# Pioneer_Kit_Shield.net
KiCad netlist of a schematic drawn in EAGLE
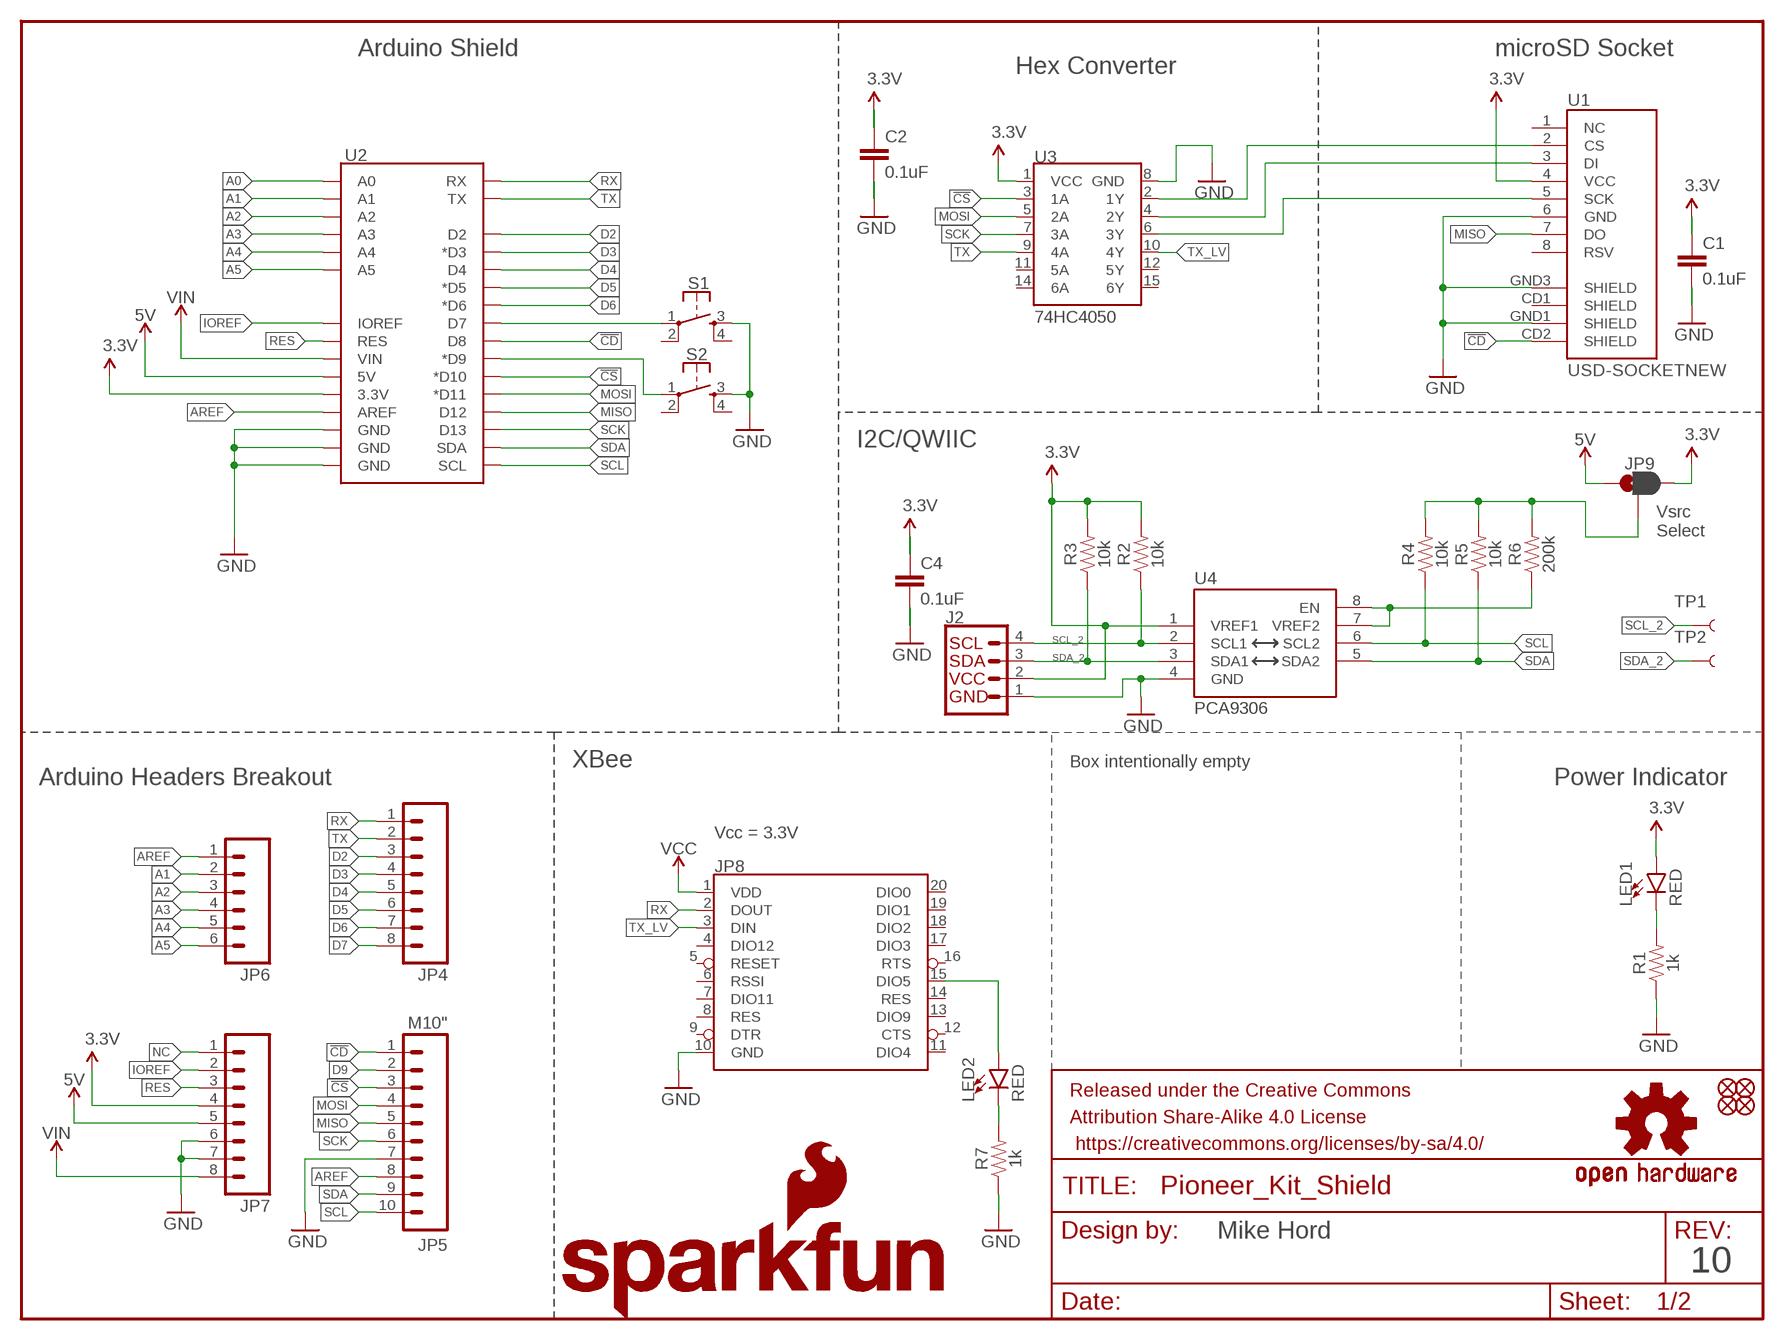
[diagram p0: schematic, sheet 1]
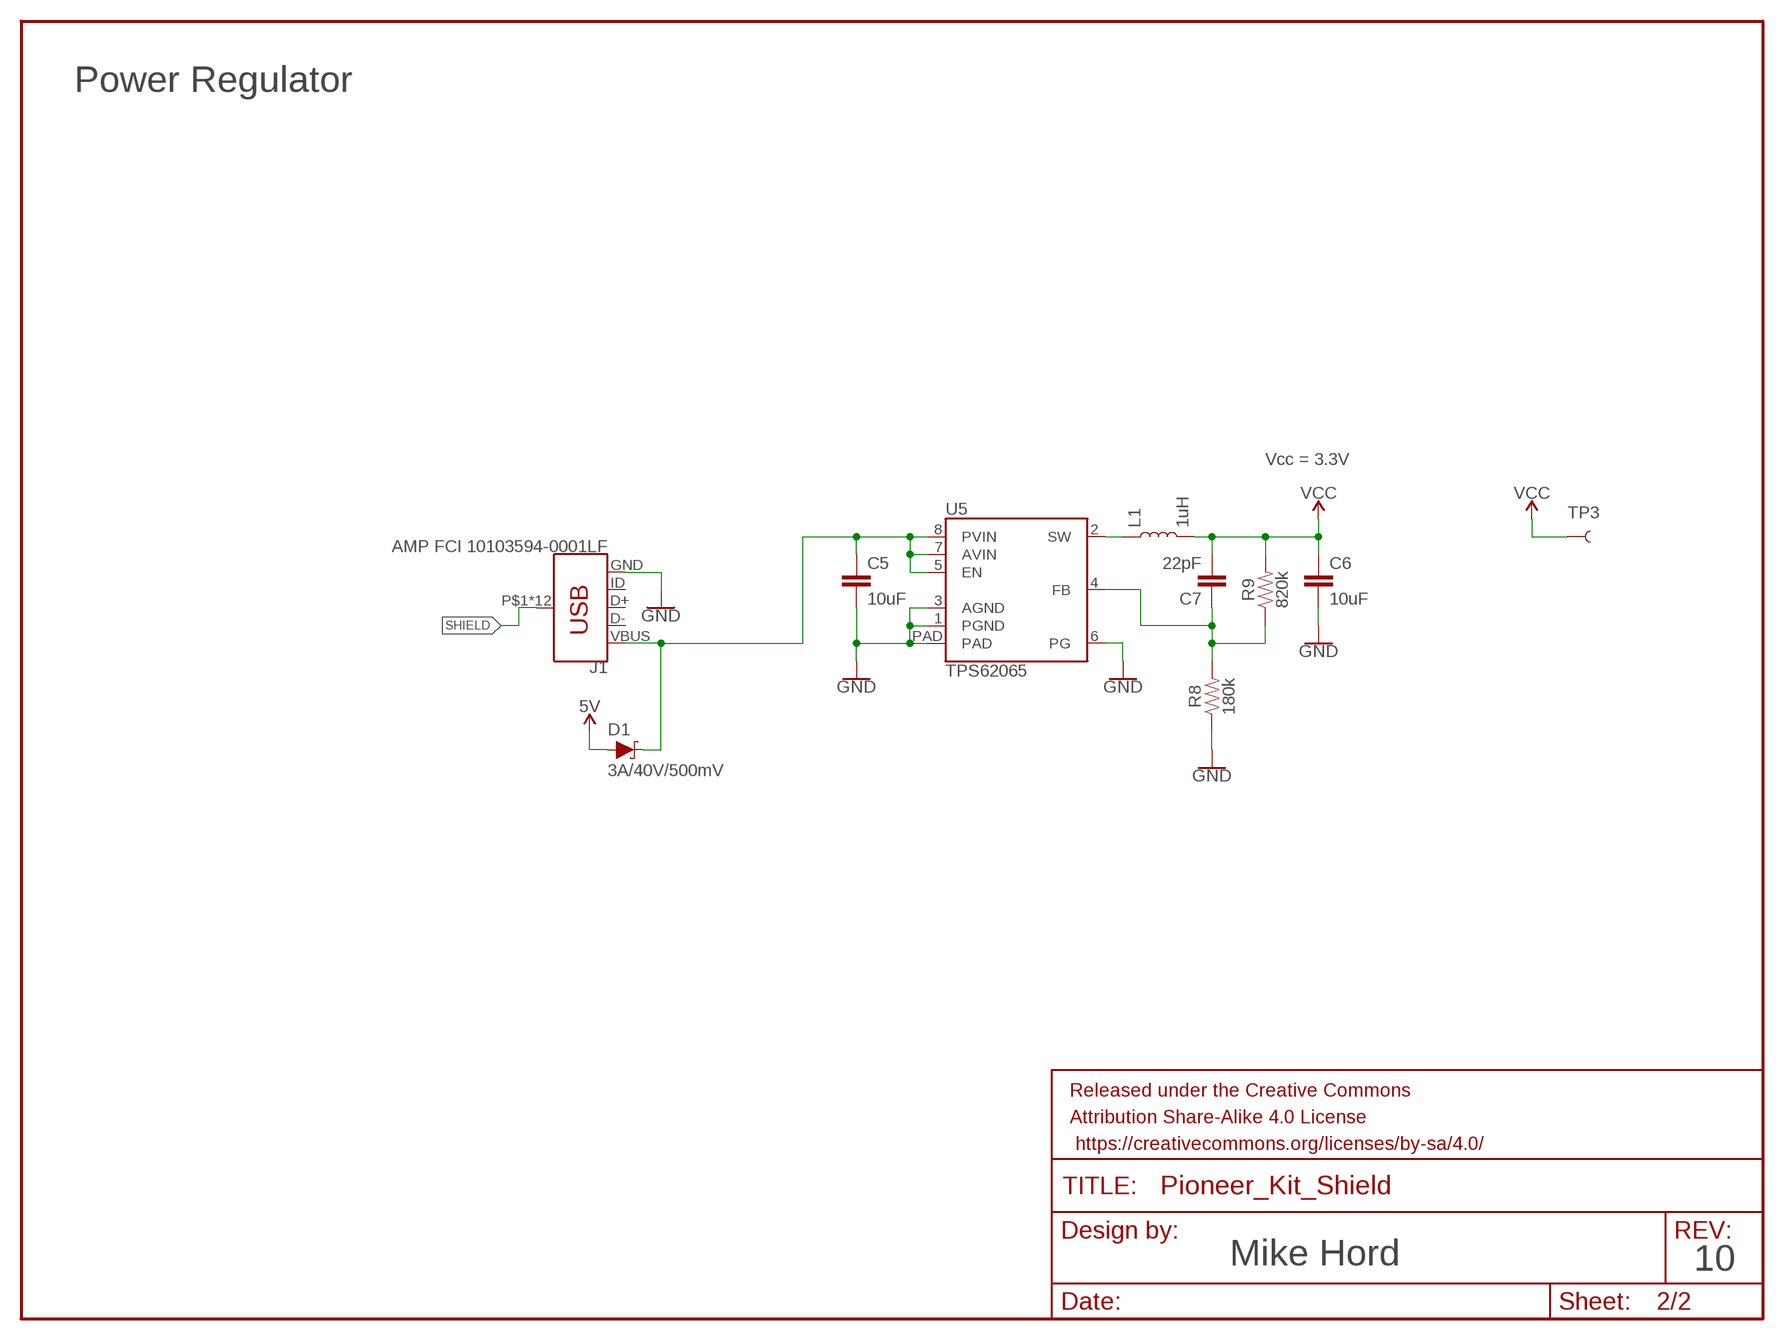
[diagram p1: schematic, sheet 2]

(export (version "E")
  (design (tool "Eeschema 10.0.6"))
  (components
    (comp (ref "C1")
      (value "0.1uF")
      (footprint "eagle-import:0603")
      (libsource (lib "eagle-import") (part "0.1UF-0603-25V-5%"))
    )
    (comp (ref "C2")
      (value "0.1uF")
      (footprint "eagle-import:0603")
      (libsource (lib "eagle-import") (part "0.1UF-0603-25V-5%"))
    )
    (comp (ref "C4")
      (value "0.1uF")
      (footprint "eagle-import:0603")
      (libsource (lib "eagle-import") (part "0.1UF-0603-25V-5%"))
    )
    (comp (ref "FRAME1")
      (value "FRAME-LETTER")
      (footprint "eagle-import:CREATIVE_COMMONS")
      (libsource (lib "eagle-import") (part "FRAME-LETTER"))
    )
    (comp (ref "J2")
      (value "QWIIC_CONNECTORJS-1MM")
      (footprint "eagle-import:1X04_1MM_RA")
      (libsource (lib "eagle-import") (part "QWIIC_CONNECTORJS-1MM"))
    )
    (comp (ref "JP1")
      (value "SFE_LOGO_NAME_FLAME.1_INCH")
      (footprint "eagle-import:SFE_LOGO_NAME_FLAME_.1")
      (libsource (lib "eagle-import") (part "SFE_LOGO_NAME_FLAME.1_INCH"))
    )
    (comp (ref "JP2")
      (value "FIDUCIAL1X2")
      (footprint "eagle-import:FIDUCIAL-1X2")
      (libsource (lib "eagle-import") (part "FIDUCIAL1X2"))
    )
    (comp (ref "JP3")
      (value "FIDUCIAL1X2")
      (footprint "eagle-import:FIDUCIAL-1X2")
      (libsource (lib "eagle-import") (part "FIDUCIAL1X2"))
    )
    (comp (ref "JP4")
      (value "M08")
      (footprint "eagle-import:1X08")
      (libsource (lib "eagle-import") (part "M08"))
    )
    (comp (ref "JP5")
      (value "M10\"")
      (footprint "eagle-import:1X10")
      (libsource (lib "eagle-import") (part "M10{dblquote}"))
    )
    (comp (ref "JP6")
      (value "M06SIP")
      (footprint "eagle-import:1X06")
      (libsource (lib "eagle-import") (part "M06SIP"))
    )
    (comp (ref "JP7")
      (value "M081X08")
      (footprint "eagle-import:1X08")
      (libsource (lib "eagle-import") (part "M081X08"))
    )
    (comp (ref "JP8")
      (value "XBEESMD")
      (footprint "eagle-import:XBEE-SMD")
      (libsource (lib "eagle-import") (part "XBEESMD"))
    )
    (comp (ref "JP9")
      (value "JUMPER-SMT_3_1-NC_PASTE_SILK")
      (footprint "eagle-import:SMT-JUMPER_3_1-NC_PASTE_SILK")
      (libsource (lib "eagle-import") (part "JUMPER-SMT_3_1-NC_PASTE_SILK"))
    )
    (comp (ref "JP10")
      (value "FIDUCIAL1X2")
      (footprint "eagle-import:FIDUCIAL-1X2")
      (libsource (lib "eagle-import") (part "FIDUCIAL1X2"))
    )
    (comp (ref "JP11")
      (value "FIDUCIAL1X2")
      (footprint "eagle-import:FIDUCIAL-1X2")
      (libsource (lib "eagle-import") (part "FIDUCIAL1X2"))
    )
    (comp (ref "LED1")
      (value "RED")
      (footprint "eagle-import:LED-0603")
      (libsource (lib "eagle-import") (part "LED-RED0603"))
    )
    (comp (ref "LED2")
      (value "RED")
      (footprint "eagle-import:LED-0603")
      (libsource (lib "eagle-import") (part "LED-RED0603"))
    )
    (comp (ref "LOGO1")
      (value "OSHW-LOGOM")
      (footprint "eagle-import:OSHW-LOGO-M")
      (libsource (lib "eagle-import") (part "OSHW-LOGOM"))
    )
    (comp (ref "R1")
      (value "1k")
      (footprint "eagle-import:0603")
      (libsource (lib "eagle-import") (part "1KOHM-0603-1/10W-1%"))
    )
    (comp (ref "R2")
      (value "10k")
      (footprint "eagle-import:0603")
      (libsource (lib "eagle-import") (part "10KOHM-0603-1/10W-1%"))
    )
    (comp (ref "R3")
      (value "10k")
      (footprint "eagle-import:0603")
      (libsource (lib "eagle-import") (part "10KOHM-0603-1/10W-1%"))
    )
    (comp (ref "R4")
      (value "10k")
      (footprint "eagle-import:0603")
      (libsource (lib "eagle-import") (part "10KOHM-0603-1/10W-1%"))
    )
    (comp (ref "R5")
      (value "10k")
      (footprint "eagle-import:0603")
      (libsource (lib "eagle-import") (part "10KOHM-0603-1/10W-1%"))
    )
    (comp (ref "R6")
      (value "200k")
      (footprint "eagle-import:0603")
      (libsource (lib "eagle-import") (part "200KOHM-0603-1/10W-1%"))
    )
    (comp (ref "R7")
      (value "1k")
      (footprint "eagle-import:0603")
      (libsource (lib "eagle-import") (part "1KOHM-0603-1/10W-1%"))
    )
    (comp (ref "S1")
      (value "MOMENTARY-SWITCH-SPST-2-SMD-5.2MM")
      (footprint "eagle-import:TACTILE_SWITCH_SMD_5.2MM")
      (libsource (lib "eagle-import") (part "MOMENTARY-SWITCH-SPST-2-SMD-5.2MM"))
    )
    (comp (ref "S2")
      (value "MOMENTARY-SWITCH-SPST-2-SMD-5.2MM")
      (footprint "eagle-import:TACTILE_SWITCH_SMD_5.2MM")
      (libsource (lib "eagle-import") (part "MOMENTARY-SWITCH-SPST-2-SMD-5.2MM"))
    )
    (comp (ref "TP1")
      (value "TEST-POINTTP_15TH_THRU")
      (footprint "eagle-import:TP_15TH")
      (libsource (lib "eagle-import") (part "TEST-POINTTP_15TH_THRU"))
    )
    (comp (ref "TP2")
      (value "TEST-POINTTP_15TH_THRU")
      (footprint "eagle-import:TP_15TH")
      (libsource (lib "eagle-import") (part "TEST-POINTTP_15TH_THRU"))
    )
    (comp (ref "U1")
      (value "USD-SOCKETNEW")
      (footprint "eagle-import:MICRO-SD-SOCKET-PP")
      (libsource (lib "eagle-import") (part "USD-SOCKETNEW"))
    )
    (comp (ref "U2")
      (value "ARDUINO_UNO_R3_SHIELDUNO_R3_SHIELD_NOLABELS_LOCK")
      (footprint "eagle-import:UNO_R3_SHIELD_NOLABELS_LOCK")
      (libsource (lib "eagle-import") (part "ARDUINO_UNO_R3_SHIELDUNO_R3_SHIELD_NOLABELS_LOCK"))
    )
    (comp (ref "U3")
      (value "74HC4050")
      (footprint "eagle-import:SO16")
      (libsource (lib "eagle-import") (part "HEX_CONVERTER"))
    )
    (comp (ref "U4")
      (value "PCA9306")
      (footprint "eagle-import:PCA9306DC")
      (libsource (lib "eagle-import") (part "PCA9306PCA9306DC-1{colon}1"))
    )
    (comp (ref "C5")
      (value "10uF")
      (footprint "eagle-import:0805")
      (libsource (lib "eagle-import") (part "10UF-0805-10V-10%"))
    )
    (comp (ref "C6")
      (value "10uF")
      (footprint "eagle-import:0603")
      (libsource (lib "eagle-import") (part "10UF-0603-6.3V-20%"))
    )
    (comp (ref "C7")
      (value "22pF")
      (footprint "eagle-import:0603")
      (libsource (lib "eagle-import") (part "22PF-0603-50V-5%"))
    )
    (comp (ref "D1")
      (value "3A/40V/500mV")
      (footprint "eagle-import:SMA-DIODE")
      (libsource (lib "eagle-import") (part "DIODE-SCHOTTKY-B340A"))
    )
    (comp (ref "FRAME2")
      (value "FRAME-LETTERNO_PACKAGE")
      (footprint "eagle-import:DUMMY")
      (fields (field (name "DESIGNER") "Nobody"))
      (libsource (lib "eagle-import") (part "FRAME-LETTERNO_PACKAGE"))
    )
    (comp (ref "J1")
      (value "AMP FCI 10103594-0001LF")
      (footprint "eagle-import:USB-MICROB-PTH")
      (libsource (lib "eagle-import") (part "USB_MICRO-B_HALF_PTH"))
    )
    (comp (ref "L1")
      (value "1uH")
      (footprint "eagle-import:INDUCTOR-SRP4020")
      (libsource (lib "eagle-import") (part "INDUCTOR-SRP4020-1UH"))
    )
    (comp (ref "R8")
      (value "180k")
      (footprint "eagle-import:0603")
      (libsource (lib "eagle-import") (part "180KOHM-0603-1/10W-1%"))
    )
    (comp (ref "R9")
      (value "820k")
      (footprint "eagle-import:0603")
      (libsource (lib "eagle-import") (part "820KOHM-0603-1/10W-1%"))
    )
    (comp (ref "TP3")
      (value "TEST-POINTTP_15TH_THRU")
      (footprint "eagle-import:TP_15TH")
      (libsource (lib "eagle-import") (part "TEST-POINTTP_15TH_THRU"))
    )
    (comp (ref "U5")
      (value "TPS62065")
      (footprint "eagle-import:WSON-8-PAD")
      (libsource (lib "eagle-import") (part "TPS62065"))
    )
  )
  (nets
    (net (code "1") (name "3.3V") (class "Default")
      (node (ref "C1") (pin "1") (pinfunction "1_1") (pintype "passive"))
      (node (ref "C2") (pin "1") (pinfunction "1_1") (pintype "passive"))
      (node (ref "C4") (pin "1") (pinfunction "1_1") (pintype "passive"))
      (node (ref "J2") (pin "2") (pinfunction "VCC_2") (pintype "power_in"))
      (node (ref "JP7") (pin "4") (pinfunction "4_4") (pintype "passive"))
      (node (ref "JP9") (pin "3") (pinfunction "3_3") (pintype "passive"))
      (node (ref "LED1") (pin "A") (pinfunction "A_A") (pintype "passive"))
      (node (ref "R2") (pin "2") (pinfunction "2_2") (pintype "passive"))
      (node (ref "R3") (pin "2") (pinfunction "2_2") (pintype "passive"))
      (node (ref "U1") (pin "4") (pinfunction "VCC_4") (pintype "bidirectional"))
      (node (ref "U2") (pin "3.3V") (pinfunction "3.3V_3.3V") (pintype "bidirectional"))
      (node (ref "U3") (pin "1") (pinfunction "VCC_1") (pintype "bidirectional"))
      (node (ref "U4") (pin "1") (pinfunction "VREF1_1") (pintype "bidirectional"))
    )
    (net (code "2") (name "5V") (class "Default")
      (node (ref "D1") (pin "A") (pinfunction "A_A") (pintype "passive"))
      (node (ref "JP7") (pin "5") (pinfunction "5_5") (pintype "passive"))
      (node (ref "JP9") (pin "1") (pinfunction "1_1") (pintype "passive"))
      (node (ref "U2") (pin "5V") (pinfunction "5V_5V") (pintype "bidirectional"))
    )
    (net (code "3") (name "A0") (class "Default")
      (node (ref "JP6") (pin "1") (pinfunction "1_1") (pintype "passive"))
      (node (ref "U2") (pin "A0") (pinfunction "A0_A0") (pintype "bidirectional"))
    )
    (net (code "4") (name "A1") (class "Default")
      (node (ref "JP6") (pin "2") (pinfunction "2_2") (pintype "passive"))
      (node (ref "U2") (pin "A1") (pinfunction "A1_A1") (pintype "bidirectional"))
    )
    (net (code "5") (name "A2") (class "Default")
      (node (ref "JP6") (pin "3") (pinfunction "3_3") (pintype "passive"))
      (node (ref "U2") (pin "A2") (pinfunction "A2_A2") (pintype "bidirectional"))
    )
    (net (code "6") (name "A3") (class "Default")
      (node (ref "JP6") (pin "4") (pinfunction "4_4") (pintype "passive"))
      (node (ref "U2") (pin "A3") (pinfunction "A3_A3") (pintype "bidirectional"))
    )
    (net (code "7") (name "A4") (class "Default")
      (node (ref "JP6") (pin "5") (pinfunction "5_5") (pintype "passive"))
      (node (ref "U2") (pin "A4") (pinfunction "A4_A4") (pintype "bidirectional"))
    )
    (net (code "8") (name "A5") (class "Default")
      (node (ref "JP6") (pin "6") (pinfunction "6_6") (pintype "passive"))
      (node (ref "U2") (pin "A5") (pinfunction "A5_A5") (pintype "bidirectional"))
    )
    (net (code "9") (name "AREF") (class "Default")
      (node (ref "JP5") (pin "8") (pinfunction "8_8") (pintype "passive"))
      (node (ref "U2") (pin "AREF") (pinfunction "AREF_AREF") (pintype "bidirectional"))
    )
    (net (code "10") (name "D2") (class "Default")
      (node (ref "JP4") (pin "3") (pinfunction "3_3") (pintype "passive"))
      (node (ref "U2") (pin "D2") (pinfunction "D2_D2") (pintype "bidirectional"))
    )
    (net (code "11") (name "D3") (class "Default")
      (node (ref "JP4") (pin "4") (pinfunction "4_4") (pintype "passive"))
      (node (ref "U2") (pin "D3") (pinfunction "*D3_D3") (pintype "bidirectional"))
    )
    (net (code "12") (name "D4") (class "Default")
      (node (ref "JP4") (pin "5") (pinfunction "5_5") (pintype "passive"))
      (node (ref "U2") (pin "D4") (pinfunction "D4_D4") (pintype "bidirectional"))
    )
    (net (code "13") (name "D5") (class "Default")
      (node (ref "JP4") (pin "6") (pinfunction "6_6") (pintype "passive"))
      (node (ref "U2") (pin "D5") (pinfunction "*D5_D5") (pintype "bidirectional"))
    )
    (net (code "14") (name "D6") (class "Default")
      (node (ref "JP4") (pin "7") (pinfunction "7_7") (pintype "passive"))
      (node (ref "U2") (pin "D6") (pinfunction "*D6_D6") (pintype "bidirectional"))
    )
    (net (code "15") (name "D7") (class "Default")
      (node (ref "JP4") (pin "8") (pinfunction "8_8") (pintype "passive"))
      (node (ref "S1") (pin "1") (pinfunction "1_1") (pintype "passive"))
      (node (ref "U2") (pin "D7") (pinfunction "D7_D7") (pintype "bidirectional"))
    )
    (net (code "16") (name "D9") (class "Default")
      (node (ref "JP5") (pin "2") (pinfunction "2_2") (pintype "passive"))
      (node (ref "S2") (pin "1") (pinfunction "1_1") (pintype "passive"))
      (node (ref "U2") (pin "D9") (pinfunction "*D9_D9") (pintype "bidirectional"))
    )
    (net (code "17") (name "GND") (class "Default")
      (node (ref "C1") (pin "2") (pinfunction "2_2") (pintype "passive"))
      (node (ref "C2") (pin "2") (pinfunction "2_2") (pintype "passive"))
      (node (ref "C4") (pin "2") (pinfunction "2_2") (pintype "passive"))
      (node (ref "C5") (pin "2") (pinfunction "2_2") (pintype "passive"))
      (node (ref "C6") (pin "2") (pinfunction "2_2") (pintype "passive"))
      (node (ref "J1") (pin "GND") (pinfunction "GND_GND") (pintype "power_in"))
      (node (ref "J2") (pin "1") (pinfunction "GND_1") (pintype "power_in"))
      (node (ref "JP5") (pin "7") (pinfunction "7_7") (pintype "passive"))
      (node (ref "JP7") (pin "6") (pinfunction "6_6") (pintype "passive"))
      (node (ref "JP7") (pin "7") (pinfunction "7_7") (pintype "passive"))
      (node (ref "JP8") (pin "10") (pinfunction "GND_10") (pintype "power_in"))
      (node (ref "R1") (pin "1") (pinfunction "1_1") (pintype "passive"))
      (node (ref "R7") (pin "1") (pinfunction "1_1") (pintype "passive"))
      (node (ref "R8") (pin "1") (pinfunction "1_1") (pintype "passive"))
      (node (ref "S1") (pin "3") (pinfunction "3_3") (pintype "passive"))
      (node (ref "S2") (pin "3") (pinfunction "3_3") (pintype "passive"))
      (node (ref "U1") (pin "6") (pinfunction "GND_6") (pintype "bidirectional"))
      (node (ref "U1") (pin "GND1") (pinfunction "SHIELD_GND1") (pintype "bidirectional"))
      (node (ref "U1") (pin "GND3") (pinfunction "SHIELD_GND3") (pintype "bidirectional"))
      (node (ref "U2") (pin "GND@0") (pinfunction "GND_GND@0") (pintype "bidirectional"))
      (node (ref "U2") (pin "GND@1") (pinfunction "GND_GND@1") (pintype "bidirectional"))
      (node (ref "U2") (pin "GND@2") (pinfunction "GND_GND@2") (pintype "bidirectional"))
      (node (ref "U3") (pin "8") (pinfunction "GND_8") (pintype "bidirectional"))
      (node (ref "U4") (pin "4") (pinfunction "GND_4") (pintype "bidirectional"))
      (node (ref "U5") (pin "1") (pinfunction "PGND_1") (pintype "bidirectional"))
      (node (ref "U5") (pin "3") (pinfunction "AGND_3") (pintype "bidirectional"))
      (node (ref "U5") (pin "6") (pinfunction "PG_6") (pintype "bidirectional"))
      (node (ref "U5") (pin "PAD") (pinfunction "PAD_PAD") (pintype "bidirectional"))
    )
    (net (code "18") (name "IOREF") (class "Default")
      (node (ref "JP7") (pin "2") (pinfunction "2_2") (pintype "passive"))
      (node (ref "U2") (pin "IOREF") (pinfunction "IOREF_IOREF") (pintype "bidirectional"))
    )
    (net (code "19") (name "MISO") (class "Default")
      (node (ref "JP5") (pin "5") (pinfunction "5_5") (pintype "passive"))
      (node (ref "U1") (pin "7") (pinfunction "DO_7") (pintype "bidirectional"))
      (node (ref "U2") (pin "D12") (pinfunction "D12_D12") (pintype "bidirectional"))
    )
    (net (code "20") (name "MOSI") (class "Default")
      (node (ref "JP5") (pin "4") (pinfunction "4_4") (pintype "passive"))
      (node (ref "U2") (pin "D11") (pinfunction "*D11_D11") (pintype "bidirectional"))
      (node (ref "U3") (pin "5") (pinfunction "2A_5") (pintype "bidirectional"))
    )
    (net (code "21") (name "NC") (class "Default")
      (node (ref "JP7") (pin "1") (pinfunction "1_1") (pintype "passive"))
    )
    (net (code "22") (name "Net-(JP8-DIO5)") (class "Default")
      (node (ref "JP8") (pin "15") (pinfunction "DIO5_15") (pintype "bidirectional"))
      (node (ref "LED2") (pin "A") (pinfunction "A_A") (pintype "passive"))
    )
    (net (code "23") (name "Net-(JP9-Pad2)") (class "Default")
      (node (ref "JP9") (pin "2") (pinfunction "2_2") (pintype "passive"))
      (node (ref "R4") (pin "2") (pinfunction "2_2") (pintype "passive"))
      (node (ref "R5") (pin "2") (pinfunction "2_2") (pintype "passive"))
      (node (ref "R6") (pin "2") (pinfunction "2_2") (pintype "passive"))
    )
    (net (code "24") (name "Net-(L1-1)") (class "Default")
      (node (ref "L1") (pin "P$1") (pinfunction "1_P$1") (pintype "passive"))
      (node (ref "U5") (pin "2") (pinfunction "SW_2") (pintype "bidirectional"))
    )
    (net (code "25") (name "Net-(LED1-PadC)") (class "Default")
      (node (ref "LED1") (pin "C") (pinfunction "C_C") (pintype "passive"))
      (node (ref "R1") (pin "2") (pinfunction "2_2") (pintype "passive"))
    )
    (net (code "26") (name "Net-(LED2-PadC)") (class "Default")
      (node (ref "LED2") (pin "C") (pinfunction "C_C") (pintype "passive"))
      (node (ref "R7") (pin "2") (pinfunction "2_2") (pintype "passive"))
    )
    (net (code "27") (name "Net-(U1-CS)") (class "Default")
      (node (ref "U1") (pin "2") (pinfunction "CS_2") (pintype "bidirectional"))
      (node (ref "U3") (pin "2") (pinfunction "1Y_2") (pintype "bidirectional"))
    )
    (net (code "28") (name "Net-(U1-DI)") (class "Default")
      (node (ref "U1") (pin "3") (pinfunction "DI_3") (pintype "bidirectional"))
      (node (ref "U3") (pin "4") (pinfunction "2Y_4") (pintype "bidirectional"))
    )
    (net (code "29") (name "Net-(U1-SCK)") (class "Default")
      (node (ref "U1") (pin "5") (pinfunction "SCK_5") (pintype "bidirectional"))
      (node (ref "U3") (pin "6") (pinfunction "3Y_6") (pintype "bidirectional"))
    )
    (net (code "30") (name "Net-(U4-EN)") (class "Default")
      (node (ref "R6") (pin "1") (pinfunction "1_1") (pintype "passive"))
      (node (ref "U4") (pin "7") (pinfunction "VREF2_7") (pintype "bidirectional"))
      (node (ref "U4") (pin "8") (pinfunction "EN_8") (pintype "bidirectional"))
    )
    (net (code "31") (name "Net-(U5-AVIN)") (class "Default")
      (node (ref "C5") (pin "1") (pinfunction "1_1") (pintype "passive"))
      (node (ref "D1") (pin "C") (pinfunction "C_C") (pintype "passive"))
      (node (ref "J1") (pin "VBUS") (pinfunction "VBUS_VBUS") (pintype "power_in"))
      (node (ref "U5") (pin "5") (pinfunction "EN_5") (pintype "bidirectional"))
      (node (ref "U5") (pin "7") (pinfunction "AVIN_7") (pintype "bidirectional"))
      (node (ref "U5") (pin "8") (pinfunction "PVIN_8") (pintype "bidirectional"))
    )
    (net (code "32") (name "Net-(U5-FB)") (class "Default")
      (node (ref "C7") (pin "1") (pinfunction "1_1") (pintype "passive"))
      (node (ref "R8") (pin "2") (pinfunction "2_2") (pintype "passive"))
      (node (ref "R9") (pin "1") (pinfunction "1_1") (pintype "passive"))
      (node (ref "U5") (pin "4") (pinfunction "FB_4") (pintype "bidirectional"))
    )
    (net (code "33") (name "RES") (class "Default")
      (node (ref "JP7") (pin "3") (pinfunction "3_3") (pintype "passive"))
      (node (ref "U2") (pin "RES") (pinfunction "RES_RES") (pintype "bidirectional"))
    )
    (net (code "34") (name "RX") (class "Default")
      (node (ref "JP4") (pin "1") (pinfunction "1_1") (pintype "passive"))
      (node (ref "JP8") (pin "2") (pinfunction "DOUT_2") (pintype "output"))
      (node (ref "U2") (pin "RX") (pinfunction "RX_RX") (pintype "bidirectional"))
    )
    (net (code "35") (name "SCK") (class "Default")
      (node (ref "JP5") (pin "6") (pinfunction "6_6") (pintype "passive"))
      (node (ref "U2") (pin "D13") (pinfunction "D13_D13") (pintype "bidirectional"))
      (node (ref "U3") (pin "7") (pinfunction "3A_7") (pintype "bidirectional"))
    )
    (net (code "36") (name "SCL") (class "Default")
      (node (ref "JP5") (pin "10") (pinfunction "10_10") (pintype "passive"))
      (node (ref "R4") (pin "1") (pinfunction "1_1") (pintype "passive"))
      (node (ref "U2") (pin "SCL") (pinfunction "SCL_SCL") (pintype "bidirectional"))
      (node (ref "U4") (pin "6") (pinfunction "SCL2_6") (pintype "bidirectional"))
    )
    (net (code "37") (name "SCL_2") (class "Default")
      (node (ref "J2") (pin "4") (pinfunction "SCL_4") (pintype "passive"))
      (node (ref "R2") (pin "1") (pinfunction "1_1") (pintype "passive"))
      (node (ref "TP1") (pin "P$1") (pinfunction "1_P$1") (pintype "bidirectional"))
      (node (ref "U4") (pin "2") (pinfunction "SCL1_2") (pintype "bidirectional"))
    )
    (net (code "38") (name "SDA") (class "Default")
      (node (ref "JP5") (pin "9") (pinfunction "9_9") (pintype "passive"))
      (node (ref "R5") (pin "1") (pinfunction "1_1") (pintype "passive"))
      (node (ref "U2") (pin "SDA") (pinfunction "SDA_SDA") (pintype "bidirectional"))
      (node (ref "U4") (pin "5") (pinfunction "SDA2_5") (pintype "bidirectional"))
    )
    (net (code "39") (name "SDA_2") (class "Default")
      (node (ref "J2") (pin "3") (pinfunction "SDA_3") (pintype "passive"))
      (node (ref "R3") (pin "1") (pinfunction "1_1") (pintype "passive"))
      (node (ref "TP2") (pin "P$1") (pinfunction "1_P$1") (pintype "bidirectional"))
      (node (ref "U4") (pin "3") (pinfunction "SDA1_3") (pintype "bidirectional"))
    )
    (net (code "40") (name "SHIELD") (class "Default")
      (node (ref "J1") (pin "P$1") (pinfunction "SHIELD_P$1") (pintype "bidirectional"))
      (node (ref "J1") (pin "P$10") (pinfunction "SHIELD_P$10") (pintype "bidirectional"))
      (node (ref "J1") (pin "P$12") (pinfunction "SHIELD_P$12") (pintype "bidirectional"))
      (node (ref "J1") (pin "P$2") (pinfunction "SHIELD_P$2") (pintype "bidirectional"))
      (node (ref "J1") (pin "P$3") (pinfunction "SHIELD_P$3") (pintype "bidirectional"))
      (node (ref "J1") (pin "P$4") (pinfunction "SHIELD_P$4") (pintype "bidirectional"))
      (node (ref "J1") (pin "P$6") (pinfunction "SHIELD_P$6") (pintype "bidirectional"))
      (node (ref "J1") (pin "P$8") (pinfunction "SHIELD_P$8") (pintype "bidirectional"))
      (node (ref "J1") (pin "SHEILD2") (pinfunction "SHIELD_SHEILD2") (pintype "bidirectional"))
      (node (ref "J1") (pin "SHIELD") (pinfunction "SHIELD_SHIELD") (pintype "bidirectional"))
      (node (ref "J1") (pin "SHIELD3") (pinfunction "SHIELD_SHIELD3") (pintype "bidirectional"))
      (node (ref "J1") (pin "SHIELD4") (pinfunction "SHIELD_SHIELD4") (pintype "bidirectional"))
    )
    (net (code "41") (name "TX") (class "Default")
      (node (ref "JP4") (pin "2") (pinfunction "2_2") (pintype "passive"))
      (node (ref "U2") (pin "TX") (pinfunction "TX_TX") (pintype "bidirectional"))
      (node (ref "U3") (pin "9") (pinfunction "4A_9") (pintype "bidirectional"))
    )
    (net (code "42") (name "TX_LV") (class "Default")
      (node (ref "JP8") (pin "3") (pinfunction "DIN_3") (pintype "input"))
      (node (ref "U3") (pin "10") (pinfunction "4Y_10") (pintype "bidirectional"))
    )
    (net (code "43") (name "VCC") (class "Default")
      (node (ref "C6") (pin "1") (pinfunction "1_1") (pintype "passive"))
      (node (ref "C7") (pin "2") (pinfunction "2_2") (pintype "passive"))
      (node (ref "JP8") (pin "1") (pinfunction "VDD_1") (pintype "power_in"))
      (node (ref "L1") (pin "P$2") (pinfunction "2_P$2") (pintype "passive"))
      (node (ref "R9") (pin "2") (pinfunction "2_2") (pintype "passive"))
      (node (ref "TP3") (pin "P$1") (pinfunction "1_P$1") (pintype "bidirectional"))
    )
    (net (code "44") (name "VIN") (class "Default")
      (node (ref "JP7") (pin "8") (pinfunction "8_8") (pintype "passive"))
      (node (ref "U2") (pin "VIN") (pinfunction "VIN_VIN") (pintype "bidirectional"))
    )
    (net (code "45") (name "unconnected-(J1-PadD+)") (class "Default")
      (node (ref "J1") (pin "D+") (pinfunction "D+_D+") (pintype "bidirectional"))
    )
    (net (code "46") (name "unconnected-(J1-PadD-)") (class "Default")
      (node (ref "J1") (pin "D-") (pinfunction "D-_D-") (pintype "bidirectional"))
    )
    (net (code "47") (name "unconnected-(J1-PadID)") (class "Default")
      (node (ref "J1") (pin "ID") (pinfunction "ID_ID") (pintype "bidirectional"))
    )
    (net (code "48") (name "unconnected-(JP8-CTS-Pad12)") (class "Default")
      (node (ref "JP8") (pin "12") (pinfunction "CTS_12") (pintype "output"))
    )
    (net (code "49") (name "unconnected-(JP8-DIO0-Pad20)") (class "Default")
      (node (ref "JP8") (pin "20") (pinfunction "DIO0_20") (pintype "bidirectional"))
    )
    (net (code "50") (name "unconnected-(JP8-DIO1-Pad19)") (class "Default")
      (node (ref "JP8") (pin "19") (pinfunction "DIO1_19") (pintype "bidirectional"))
    )
    (net (code "51") (name "unconnected-(JP8-DIO2-Pad18)") (class "Default")
      (node (ref "JP8") (pin "18") (pinfunction "DIO2_18") (pintype "bidirectional"))
    )
    (net (code "52") (name "unconnected-(JP8-DIO3-Pad17)") (class "Default")
      (node (ref "JP8") (pin "17") (pinfunction "DIO3_17") (pintype "bidirectional"))
    )
    (net (code "53") (name "unconnected-(JP8-DIO4-Pad11)") (class "Default")
      (node (ref "JP8") (pin "11") (pinfunction "DIO4_11") (pintype "bidirectional"))
    )
    (net (code "54") (name "unconnected-(JP8-DIO9-Pad13)") (class "Default")
      (node (ref "JP8") (pin "13") (pinfunction "DIO9_13") (pintype "bidirectional"))
    )
    (net (code "55") (name "unconnected-(JP8-DIO11-Pad7)") (class "Default")
      (node (ref "JP8") (pin "7") (pinfunction "DIO11_7") (pintype "bidirectional"))
    )
    (net (code "56") (name "unconnected-(JP8-DIO12-Pad4)") (class "Default")
      (node (ref "JP8") (pin "4") (pinfunction "DIO12_4") (pintype "bidirectional"))
    )
    (net (code "57") (name "unconnected-(JP8-DTR-Pad9)") (class "Default")
      (node (ref "JP8") (pin "9") (pinfunction "DTR_9") (pintype "bidirectional"))
    )
    (net (code "58") (name "unconnected-(JP8-RES-Pad8)") (class "Default")
      (node (ref "JP8") (pin "8") (pinfunction "RES_8") (pintype "bidirectional"))
    )
    (net (code "59") (name "unconnected-(JP8-RES-Pad14)") (class "Default")
      (node (ref "JP8") (pin "14") (pinfunction "RES_14") (pintype "bidirectional"))
    )
    (net (code "60") (name "unconnected-(JP8-RESET-Pad5)") (class "Default")
      (node (ref "JP8") (pin "5") (pinfunction "RESET_5") (pintype "input"))
    )
    (net (code "61") (name "unconnected-(JP8-RSSI-Pad6)") (class "Default")
      (node (ref "JP8") (pin "6") (pinfunction "RSSI_6") (pintype "bidirectional"))
    )
    (net (code "62") (name "unconnected-(JP8-RTS-Pad16)") (class "Default")
      (node (ref "JP8") (pin "16") (pinfunction "RTS_16") (pintype "input"))
    )
    (net (code "63") (name "unconnected-(S1-Pad2)") (class "Default")
      (node (ref "S1") (pin "2") (pinfunction "2_2") (pintype "passive"))
    )
    (net (code "64") (name "unconnected-(S1-Pad4)") (class "Default")
      (node (ref "S1") (pin "4") (pinfunction "4_4") (pintype "passive"))
    )
    (net (code "65") (name "unconnected-(S2-Pad2)") (class "Default")
      (node (ref "S2") (pin "2") (pinfunction "2_2") (pintype "passive"))
    )
    (net (code "66") (name "unconnected-(S2-Pad4)") (class "Default")
      (node (ref "S2") (pin "4") (pinfunction "4_4") (pintype "passive"))
    )
    (net (code "67") (name "unconnected-(U1-NC-Pad1)") (class "Default")
      (node (ref "U1") (pin "1") (pinfunction "NC_1") (pintype "bidirectional"))
    )
    (net (code "68") (name "unconnected-(U1-RSV-Pad8)") (class "Default")
      (node (ref "U1") (pin "8") (pinfunction "RSV_8") (pintype "bidirectional"))
    )
    (net (code "69") (name "unconnected-(U1-SHIELD-PadCD1)") (class "Default")
      (node (ref "U1") (pin "CD1") (pinfunction "SHIELD_CD1") (pintype "bidirectional"))
    )
    (net (code "70") (name "unconnected-(U3-5A-Pad11)") (class "Default")
      (node (ref "U3") (pin "11") (pinfunction "5A_11") (pintype "bidirectional"))
    )
    (net (code "71") (name "unconnected-(U3-5Y-Pad12)") (class "Default")
      (node (ref "U3") (pin "12") (pinfunction "5Y_12") (pintype "bidirectional"))
    )
    (net (code "72") (name "unconnected-(U3-6A-Pad14)") (class "Default")
      (node (ref "U3") (pin "14") (pinfunction "6A_14") (pintype "bidirectional"))
    )
    (net (code "73") (name "unconnected-(U3-6Y-Pad15)") (class "Default")
      (node (ref "U3") (pin "15") (pinfunction "6Y_15") (pintype "bidirectional"))
    )
    (net (code "74") (name "~{CD}") (class "Default")
      (node (ref "JP5") (pin "1") (pinfunction "1_1") (pintype "passive"))
      (node (ref "U1") (pin "CD2") (pinfunction "SHIELD_CD2") (pintype "bidirectional"))
      (node (ref "U2") (pin "D8") (pinfunction "D8_D8") (pintype "bidirectional"))
    )
    (net (code "75") (name "~{CS}") (class "Default")
      (node (ref "JP5") (pin "3") (pinfunction "3_3") (pintype "passive"))
      (node (ref "U2") (pin "D10") (pinfunction "*D10_D10") (pintype "bidirectional"))
      (node (ref "U3") (pin "3") (pinfunction "1A_3") (pintype "bidirectional"))
    )
  )
)
